# TP1_NodoWiFi_Cpu0_Rev0.net
KiCad netlist of a schematic drawn in Altium Designer
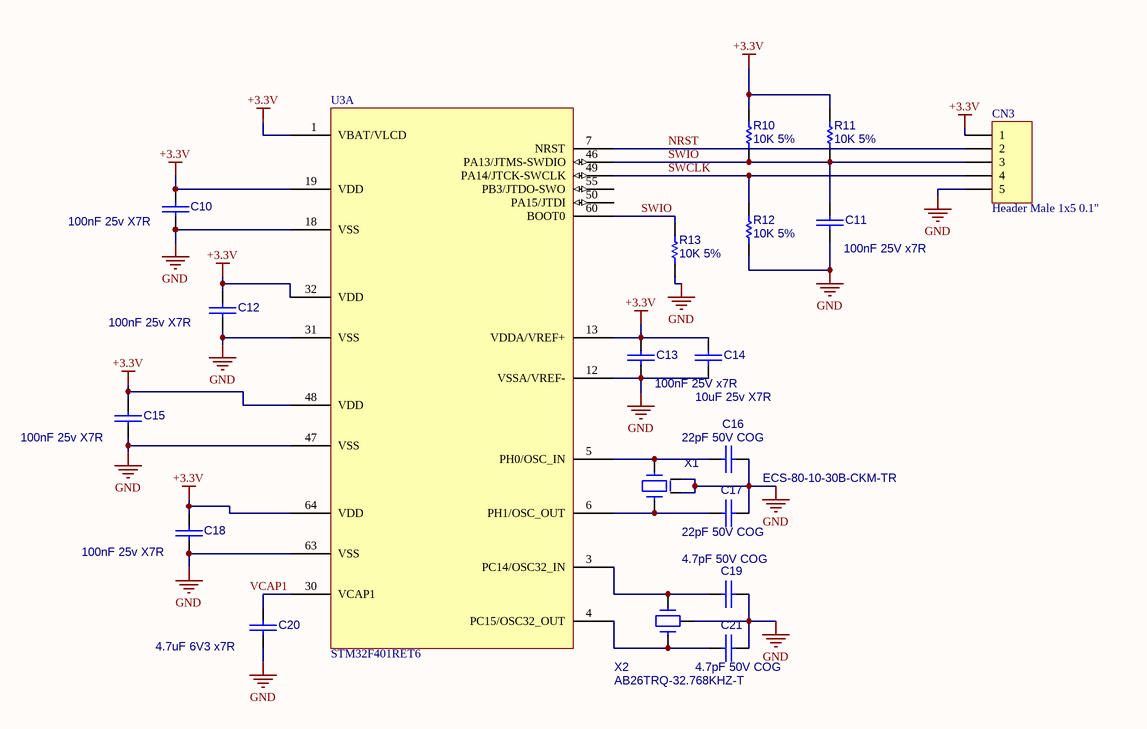
[diagram p0: TP1_NodoWiFi_Cpu0_Rev0.SchDoc]

(export (version "E")
  (design (tool "Eeschema 10.0.6"))
  (components
    (comp (ref "C10")
      (value "100nF 25v X7R")
      (footprint "IDCI_WifiNode:C_0805")
      (libsource (lib "WifiNode") (part "CAP"))
    )
    (comp (ref "C11")
      (value "100nF 25V x7R")
      (footprint "IDCI_WifiNode:C_0805")
      (description "Non Polarized Capacitor")
      (libsource (lib "WifiNode") (part "CAP"))
    )
    (comp (ref "C12") (value "100nF 25v X7R") (footprint "C_0805") (libsource (lib "WifiNode") (part "CAP")))
    (comp (ref "C13")
      (value "100nF 25V x7R")
      (footprint "C_0805")
      (description "Non Polarized Capacitor")
      (libsource (lib "WifiNode") (part "CAP"))
    )
    (comp (ref "C14")
      (value "10uF 25v X7R")
      (footprint "C_0805")
      (description "Non Polarized Capacitor")
      (libsource (lib "WifiNode") (part "CAP"))
    )
    (comp (ref "C15") (value "100nF 25v X7R") (footprint "C_0805") (libsource (lib "WifiNode") (part "CAP")))
    (comp (ref "C16")
      (value "22pF 50V COG")
      (footprint "C_0805")
      (description "Non Polarized Capacitor")
      (libsource (lib "WifiNode") (part "CAP"))
    )
    (comp (ref "C17")
      (value "22pF 50V COG")
      (footprint "C_0805")
      (description "Non Polarized Capacitor")
      (libsource (lib "WifiNode") (part "CAP"))
    )
    (comp (ref "C18") (value "100nF 25v X7R") (footprint "C_0805") (libsource (lib "WifiNode") (part "CAP")))
    (comp (ref "C19")
      (value "4.7pF 50V COG")
      (footprint "C_0805")
      (description "Non Polarized Capacitor")
      (libsource (lib "WifiNode") (part "CAP"))
    )
    (comp (ref "C20")
      (value "4.7uF 6V3 x7R")
      (footprint "IDCI_WifiNode:C_0805")
      (description "100nF 25v X7R")
      (libsource (lib "WifiNode") (part "CAP"))
    )
    (comp (ref "C21")
      (value "4.7pF 50V COG")
      (footprint "C_0805")
      (description "Non Polarized Capacitor")
      (libsource (lib "WifiNode") (part "CAP"))
    )
    (comp (ref "CN3")
      (value "Header Male 1x5 0.1\"")
      (footprint "Header_M_1x5_0.1\"")
      (description "Connector Generic 5 Vias")
      (libsource (lib "WifiNode") (part "CONN_05P"))
    )
    (comp (ref "R10")
      (value "10K 5%")
      (footprint "IDCI_WifiNode:R_0805")
      (description "Resistor")
      (libsource (lib "WifiNode") (part "Res1"))
    )
    (comp (ref "R11")
      (value "10K 5%")
      (footprint "IDCI_WifiNode:R_0805")
      (description "Resistor")
      (libsource (lib "WifiNode") (part "Res1"))
    )
    (comp (ref "R12")
      (value "10K 5%")
      (footprint "R_0805")
      (description "Resistor")
      (libsource (lib "WifiNode") (part "Res1"))
    )
    (comp (ref "R13")
      (value "10K 5%")
      (footprint "IDCI_WifiNode:R_0805")
      (description "Resistor")
      (libsource (lib "WifiNode") (part "Res1"))
    )
    (comp (ref "U3")
      (value "STM32F401RET6")
      (footprint "LQFP_64")
      (libsource (lib "WifiNode") (part "STM32F401RE"))
    )
    (comp (ref "X1")
      (value "ECS-80-10-30B-CKM-TR")
      (footprint "ABM3C")
      (description "Crystal 4 Vias + GND")
      (libsource (lib "WifiNode") (part "CRYSTAL_4P"))
    )
    (comp (ref "X2")
      (value "AB26TRQ-32.768KHZ-T")
      (footprint "AB26TQF")
      (description "Crystal 2 Vias + GND")
      (libsource (lib "WifiNode") (part "CRYSTAL 3P"))
    )
  )
  (nets
    (net (code "1") (name "+3.3V") (class "Default")
      (node (ref "C10") (pin "1") (pinfunction "1_1") (pintype "passive"))
      (node (ref "C12") (pin "1") (pinfunction "1_1") (pintype "passive"))
      (node (ref "C13") (pin "1") (pinfunction "1_1") (pintype "passive"))
      (node (ref "C14") (pin "1") (pinfunction "1_1") (pintype "passive"))
      (node (ref "C15") (pin "1") (pinfunction "1_1") (pintype "passive"))
      (node (ref "C18") (pin "1") (pinfunction "1_1") (pintype "passive"))
      (node (ref "CN3") (pin "1") (pinfunction "1_1") (pintype "passive"))
      (node (ref "R10") (pin "2") (pinfunction "2_2") (pintype "passive"))
      (node (ref "R11") (pin "2") (pinfunction "2_2") (pintype "passive"))
      (node (ref "U3") (pin "1") (pinfunction "VBAT/VLCD_1") (pintype "passive"))
      (node (ref "U3") (pin "13") (pinfunction "VDDA/VREF+_13") (pintype "passive"))
      (node (ref "U3") (pin "19") (pinfunction "VDD_19") (pintype "passive"))
      (node (ref "U3") (pin "32") (pinfunction "VDD_32") (pintype "passive"))
      (node (ref "U3") (pin "48") (pinfunction "VDD_48") (pintype "passive"))
      (node (ref "U3") (pin "64") (pinfunction "VDD_64") (pintype "passive"))
    )
    (net (code "2") (name "/NRST") (class "Default")
      (node (ref "CN3") (pin "2") (pinfunction "2_2") (pintype "passive"))
      (node (ref "U3") (pin "7") (pinfunction "NRST_7") (pintype "passive"))
    )
    (net (code "3") (name "/SWCLK") (class "Default")
      (node (ref "CN3") (pin "4") (pinfunction "4_4") (pintype "passive"))
      (node (ref "R12") (pin "2") (pinfunction "2_2") (pintype "passive"))
      (node (ref "U3") (pin "49") (pinfunction "PA14/JTCK-SWCLK_49") (pintype "bidirectional"))
    )
    (net (code "4") (name "/SWIO") (class "Default")
      (node (ref "C11") (pin "1") (pinfunction "1_1") (pintype "passive"))
      (node (ref "CN3") (pin "3") (pinfunction "3_3") (pintype "passive"))
      (node (ref "R10") (pin "1") (pinfunction "1_1") (pintype "passive"))
      (node (ref "R11") (pin "1") (pinfunction "1_1") (pintype "passive"))
      (node (ref "R13") (pin "2") (pinfunction "2_2") (pintype "passive"))
      (node (ref "U3") (pin "46") (pinfunction "PA13/JTMS-SWDIO_46") (pintype "bidirectional"))
      (node (ref "U3") (pin "60") (pinfunction "BOOT0_60") (pintype "passive"))
    )
    (net (code "6") (name "GND") (class "Default")
      (node (ref "C10") (pin "2") (pinfunction "2_2") (pintype "passive"))
      (node (ref "C11") (pin "2") (pinfunction "2_2") (pintype "passive"))
      (node (ref "C12") (pin "2") (pinfunction "2_2") (pintype "passive"))
      (node (ref "C13") (pin "2") (pinfunction "2_2") (pintype "passive"))
      (node (ref "C14") (pin "2") (pinfunction "2_2") (pintype "passive"))
      (node (ref "C15") (pin "2") (pinfunction "2_2") (pintype "passive"))
      (node (ref "C16") (pin "2") (pinfunction "2_2") (pintype "passive"))
      (node (ref "C17") (pin "2") (pinfunction "2_2") (pintype "passive"))
      (node (ref "C18") (pin "2") (pinfunction "2_2") (pintype "passive"))
      (node (ref "C19") (pin "2") (pinfunction "2_2") (pintype "passive"))
      (node (ref "C20") (pin "2") (pinfunction "2_2") (pintype "passive"))
      (node (ref "C21") (pin "2") (pinfunction "2_2") (pintype "passive"))
      (node (ref "CN3") (pin "5") (pinfunction "5_5") (pintype "passive"))
      (node (ref "R12") (pin "1") (pinfunction "1_1") (pintype "passive"))
      (node (ref "R13") (pin "1") (pinfunction "1_1") (pintype "passive"))
      (node (ref "U3") (pin "12") (pinfunction "VSSA/VREF-_12") (pintype "passive"))
      (node (ref "U3") (pin "18") (pinfunction "VSS_18") (pintype "passive"))
      (node (ref "U3") (pin "31") (pinfunction "VSS_31") (pintype "passive"))
      (node (ref "U3") (pin "47") (pinfunction "VSS_47") (pintype "passive"))
      (node (ref "U3") (pin "63") (pinfunction "VSS_63") (pintype "passive"))
      (node (ref "X1") (pin "2") (pinfunction "2_2") (pintype "passive"))
      (node (ref "X1") (pin "4") (pinfunction "4_4") (pintype "passive"))
      (node (ref "X2") (pin "3") (pinfunction "3_3") (pintype "passive"))
    )
    (net (code "7") (name "Net-(U3A-PC14{slash}OSC32_IN)") (class "Default")
      (node (ref "C19") (pin "1") (pinfunction "1_1") (pintype "passive"))
      (node (ref "U3") (pin "3") (pinfunction "PC14/OSC32_IN_3") (pintype "passive"))
      (node (ref "X2") (pin "2") (pinfunction "2_2") (pintype "passive"))
    )
    (net (code "8") (name "Net-(U3A-PC15{slash}OSC32_OUT)") (class "Default")
      (node (ref "C21") (pin "1") (pinfunction "1_1") (pintype "passive"))
      (node (ref "U3") (pin "4") (pinfunction "PC15/OSC32_OUT_4") (pintype "passive"))
      (node (ref "X2") (pin "1") (pinfunction "1_1") (pintype "passive"))
    )
    (net (code "9") (name "Net-(U3A-PH0{slash}OSC_IN)") (class "Default")
      (node (ref "C16") (pin "1") (pinfunction "1_1") (pintype "passive"))
      (node (ref "U3") (pin "5") (pinfunction "PH0/OSC_IN_5") (pintype "passive"))
      (node (ref "X1") (pin "1") (pinfunction "1_1") (pintype "passive"))
    )
    (net (code "10") (name "Net-(U3A-PH1{slash}OSC_OUT)") (class "Default")
      (node (ref "C17") (pin "1") (pinfunction "1_1") (pintype "passive"))
      (node (ref "U3") (pin "6") (pinfunction "PH1/OSC_OUT_6") (pintype "passive"))
      (node (ref "X1") (pin "3") (pinfunction "3_3") (pintype "passive"))
    )
    (net (code "11") (name "Net-(U3A-VCAP1)") (class "Default")
      (node (ref "C20") (pin "1") (pinfunction "1_1") (pintype "passive"))
      (node (ref "U3") (pin "30") (pinfunction "VCAP1_30") (pintype "passive"))
    )
    (net (code "12") (name "unconnected-(U3A-PA15{slash}JTDI-Pad50)") (class "Default")
      (node (ref "U3") (pin "50") (pinfunction "PA15/JTDI_50") (pintype "bidirectional"))
    )
    (net (code "13") (name "unconnected-(U3A-PB3{slash}JTDO-SWO-Pad55)") (class "Default")
      (node (ref "U3") (pin "55") (pinfunction "PB3/JTDO-SWO_55") (pintype "bidirectional"))
    )
  )
)
